# AFBR-RX-fiber_optic_reciever.net
KiCad netlist of a schematic drawn in Altium Designer
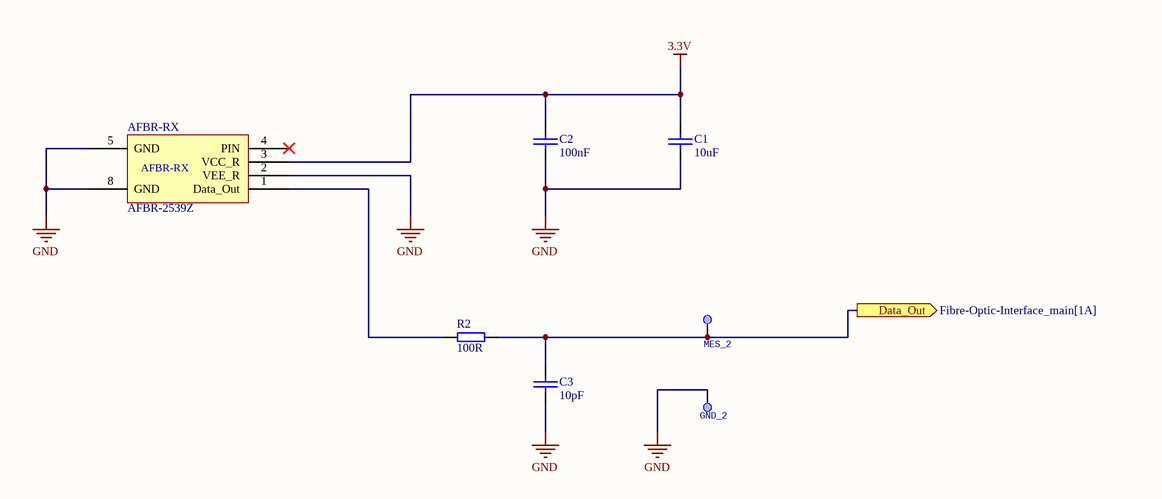
[diagram p0: AFBR-RX-fiber_optic_reciever.SchDoc]

(export (version "E")
  (design (tool "Eeschema 10.0.6"))
  (components
    (comp (ref "AFBR-RX")
      (value "AFBR-2539Z")
      (footprint "AFBR-TX/RX-HORIZONTAL")
      (description "Fiber Optic Transmitters, Receivers, Transceivers VL V 50MBd RX inv")
      (libsource (lib "fibre_optic_transmiters") (part "AFBR-RX"))
    )
    (comp (ref "C1")
      (value "10uF")
      (footprint "1206")
      (description "Capacitor")
      (libsource (lib "passive_elements") (part "C_1"))
    )
    (comp (ref "C2")
      (value "100nF")
      (footprint "0603C")
      (description "Capacitor")
      (libsource (lib "passive_elements") (part "C"))
    )
    (comp (ref "C3")
      (value "10pF")
      (footprint "0603C")
      (description "Capacitor")
      (libsource (lib "passive_elements") (part "C_3"))
    )
    (comp (ref "GND_2")
      (value "PK_1")
      (footprint "PK")
      (description "Punkt")
      (libsource (lib "others") (part "PK_1"))
    )
    (comp (ref "MES_2")
      (value "PK_1")
      (footprint "PK")
      (description "Punkt")
      (libsource (lib "others") (part "PK_1"))
    )
    (comp (ref "R2") (value "100R") (footprint "0603R") (libsource (lib "passive_elements") (part "R_1")))
  )
  (nets
    (net (code "1") (name "/Data_Out") (class "Default")
      (node (ref "C3") (pin "1") (pinfunction "1_1") (pintype "passive"))
      (node (ref "MES_2") (pin "1") (pinfunction "1_1") (pintype "passive"))
      (node (ref "R2") (pin "2") (pinfunction "2_2") (pintype "passive"))
    )
    (net (code "2") (name "3.3V") (class "Default")
      (node (ref "AFBR-RX") (pin "3") (pinfunction "VCC_R_3") (pintype "passive"))
      (node (ref "C1") (pin "1") (pinfunction "1_1") (pintype "passive"))
      (node (ref "C2") (pin "1") (pinfunction "1_1") (pintype "passive"))
    )
    (net (code "3") (name "GND") (class "Default")
      (node (ref "AFBR-RX") (pin "2") (pinfunction "VEE_R_2") (pintype "passive"))
      (node (ref "AFBR-RX") (pin "5") (pinfunction "GND_5") (pintype "passive"))
      (node (ref "AFBR-RX") (pin "8") (pinfunction "GND_8") (pintype "passive"))
      (node (ref "C1") (pin "2") (pinfunction "2_2") (pintype "passive"))
      (node (ref "C2") (pin "2") (pinfunction "2_2") (pintype "passive"))
      (node (ref "C3") (pin "2") (pinfunction "2_2") (pintype "passive"))
      (node (ref "GND_2") (pin "1") (pinfunction "1_1") (pintype "passive"))
    )
    (net (code "4") (name "Net-(AFBR-RX-Data_Out)") (class "Default")
      (node (ref "AFBR-RX") (pin "1") (pinfunction "Data_Out_1") (pintype "passive"))
      (node (ref "R2") (pin "1") (pinfunction "1_1") (pintype "passive"))
    )
    (net (code "5") (name "unconnected-(AFBR-RX-PIN-Pad4)") (class "Default")
      (node (ref "AFBR-RX") (pin "4") (pinfunction "PIN_4") (pintype "passive+no_connect"))
    )
  )
)
